# CHEAPO4.net
KiCad netlist of a schematic drawn in EAGLE
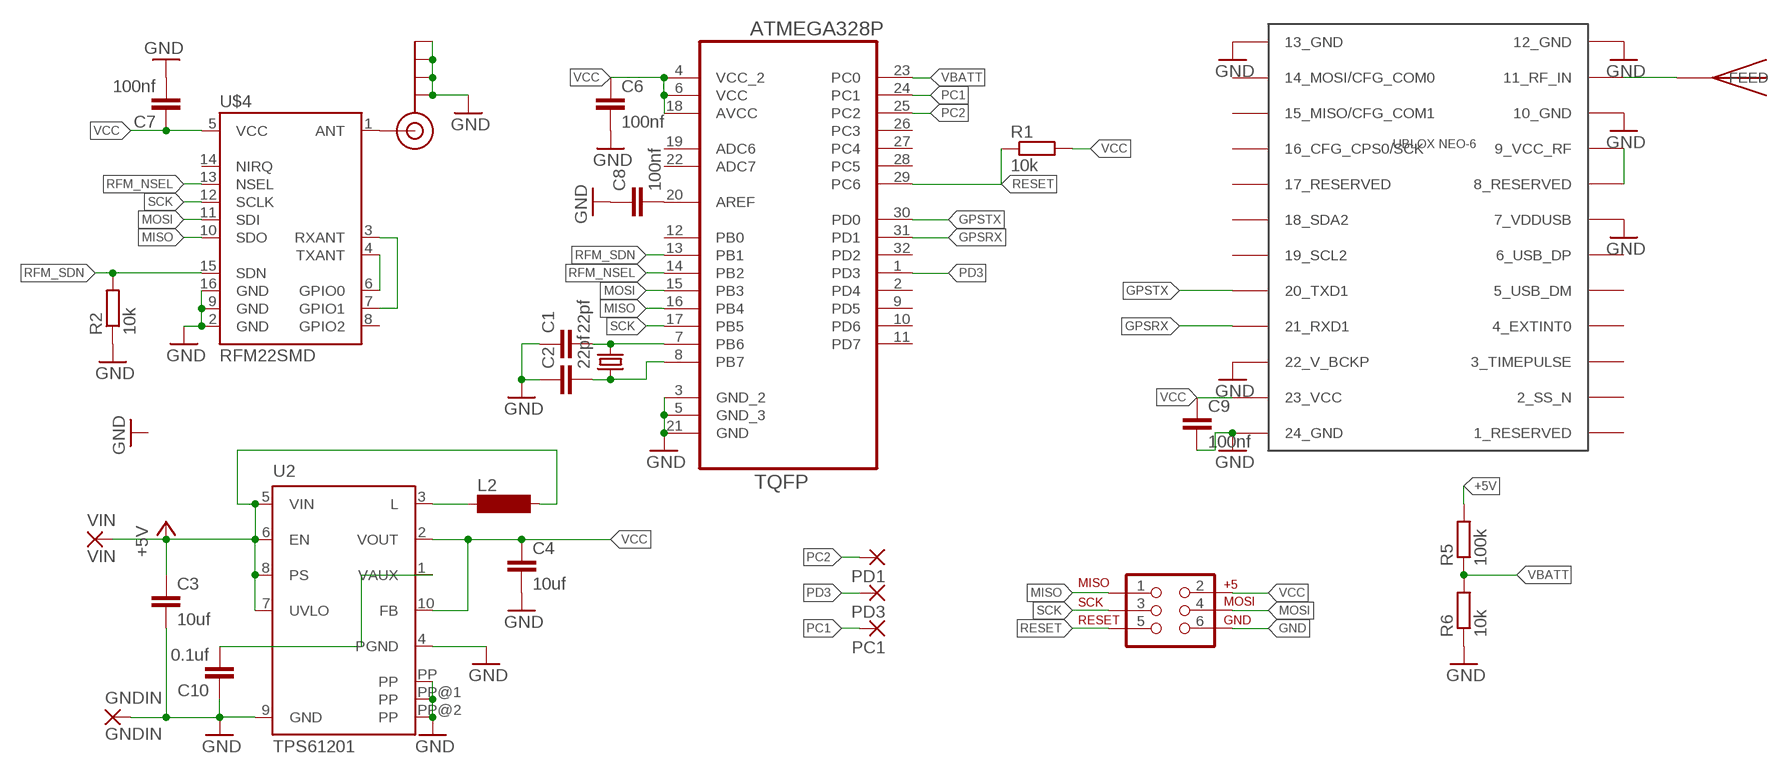
[diagram p0: schematic, sheet 1]

(export (version "E")
  (design (tool "Eeschema 10.0.6"))
  (components
    (comp (ref "C1")
      (value "22pf")
      (footprint "eagle-import:C0603")
      (libsource (lib "eagle-import") (part "C-EUC0603"))
    )
    (comp (ref "C2")
      (value "22pf")
      (footprint "eagle-import:C0603")
      (libsource (lib "eagle-import") (part "C-EUC0603"))
    )
    (comp (ref "C3")
      (value "10uf")
      (footprint "eagle-import:C1206")
      (libsource (lib "eagle-import") (part "C-EUC1206"))
    )
    (comp (ref "C4")
      (value "10uf")
      (footprint "eagle-import:C1206")
      (libsource (lib "eagle-import") (part "C-EUC1206"))
    )
    (comp (ref "C6")
      (value "100nf")
      (footprint "eagle-import:C0603")
      (libsource (lib "eagle-import") (part "C-EUC0603"))
    )
    (comp (ref "C7")
      (value "100nf")
      (footprint "eagle-import:C0603")
      (libsource (lib "eagle-import") (part "C-EUC0603"))
    )
    (comp (ref "C8")
      (value "100nf")
      (footprint "eagle-import:C0603")
      (libsource (lib "eagle-import") (part "C-EUC0603"))
    )
    (comp (ref "C9")
      (value "100nf")
      (footprint "eagle-import:C0603")
      (libsource (lib "eagle-import") (part "C-EUC0603"))
    )
    (comp (ref "C10")
      (value "0.1uf")
      (footprint "eagle-import:C0603")
      (libsource (lib "eagle-import") (part "C-EUC0603"))
    )
    (comp (ref "GNDIN")
      (value "GNDIN")
      (footprint "eagle-import:SMD1,27-2,54")
      (libsource (lib "eagle-import") (part "SMD2"))
    )
    (comp (ref "J$1")
      (value "SMA_EDGE")
      (footprint "eagle-import:SMA-EDGE")
      (libsource (lib "eagle-import") (part "SMA_EDGE"))
    )
    (comp (ref "J1")
      (value "AVR_SPI_PRG_6PTH")
      (footprint "eagle-import:2X3")
      (libsource (lib "eagle-import") (part "AVR_SPI_PRG_6PTH"))
    )
    (comp (ref "L2")
      (value "MS50")
      (footprint "eagle-import:MS50")
      (libsource (lib "eagle-import") (part "MS50"))
    )
    (comp (ref "PC1")
      (value "SMD2")
      (footprint "eagle-import:SMD1,27-2,54")
      (libsource (lib "eagle-import") (part "SMD2"))
    )
    (comp (ref "PD1")
      (value "SMD2")
      (footprint "eagle-import:SMD1,27-2,54")
      (libsource (lib "eagle-import") (part "SMD2"))
    )
    (comp (ref "PD3")
      (value "SMD2")
      (footprint "eagle-import:SMD1,27-2,54")
      (libsource (lib "eagle-import") (part "SMD2"))
    )
    (comp (ref "R1")
      (value "10k")
      (footprint "eagle-import:R0603")
      (libsource (lib "eagle-import") (part "R-EU_R0603"))
    )
    (comp (ref "R2")
      (value "10k")
      (footprint "eagle-import:R0603")
      (libsource (lib "eagle-import") (part "R-EU_R0603"))
    )
    (comp (ref "R5")
      (value "100k")
      (footprint "eagle-import:R0603")
      (libsource (lib "eagle-import") (part "R-EU_R0603"))
    )
    (comp (ref "R6")
      (value "10k")
      (footprint "eagle-import:R0603")
      (libsource (lib "eagle-import") (part "R-EU_R0603"))
    )
    (comp (ref "U$1")
      (value "UBLOX_NEO-6")
      (footprint "eagle-import:UBLOX_NEO-6P")
      (libsource (lib "eagle-import") (part "UBLOX_NEO-6"))
    )
    (comp (ref "U$2")
      (value "ABRACON_ABM3_CRYSTALABM03_HC49")
      (footprint "eagle-import:ABM03_HC49")
      (libsource (lib "eagle-import") (part "ABRACON_ABM3_CRYSTALABM03_HC49"))
    )
    (comp (ref "U$3")
      (value "JTI_ANTENNA-1575AT43A40")
      (footprint "eagle-import:JTI_ANTENNA-1575AT43A40")
      (libsource (lib "eagle-import") (part "JTI_ANTENNA-1575AT43A40"))
    )
    (comp (ref "U$4")
      (value "RFM22SMD")
      (footprint "eagle-import:RFM22-XXX-S2")
      (libsource (lib "eagle-import") (part "RFM22SMD"))
    )
    (comp (ref "U1")
      (value "ATMEGA328P-AU")
      (footprint "eagle-import:QFP80P900X900X120-32N")
      (libsource (lib "eagle-import") (part "ATMEGA328P-AU"))
    )
    (comp (ref "U2")
      (value "TPS61201")
      (footprint "eagle-import:S-PDSO-N10")
      (fields
        (field (name "MPN") "TPS61201DRCT")
        (field (name "MPN_1") "TPS61200DRCT")
        (field (name "OC_FARNELL") "1471238")
        (field (name "OC_NEWARK") "37M0066")
      )
      (libsource (lib "eagle-import") (part "TPS61201"))
    )
    (comp (ref "VIN")
      (value "VIN")
      (footprint "eagle-import:SMD1,27-2,54")
      (libsource (lib "eagle-import") (part "SMD2"))
    )
  )
  (nets
    (net (code "1") (name "+5V") (class "Default")
      (node (ref "C3") (pin "1") (pinfunction "1_1") (pintype "passive"))
      (node (ref "L2") (pin "2") (pinfunction "2_2") (pintype "passive"))
      (node (ref "R5") (pin "2") (pinfunction "2_2") (pintype "passive"))
      (node (ref "U2") (pin "5") (pinfunction "VIN_5") (pintype "input"))
      (node (ref "U2") (pin "6") (pinfunction "EN_6") (pintype "input"))
      (node (ref "U2") (pin "7") (pinfunction "UVLO_7") (pintype "input"))
      (node (ref "U2") (pin "8") (pinfunction "PS_8") (pintype "input"))
      (node (ref "VIN") (pin "1") (pinfunction "P_1") (pintype "passive"))
    )
    (net (code "2") (name "GND") (class "Default")
      (node (ref "C1") (pin "1") (pinfunction "1_1") (pintype "passive"))
      (node (ref "C10") (pin "1") (pinfunction "1_1") (pintype "passive"))
      (node (ref "C2") (pin "1") (pinfunction "1_1") (pintype "passive"))
      (node (ref "C3") (pin "2") (pinfunction "2_2") (pintype "passive"))
      (node (ref "C4") (pin "2") (pinfunction "2_2") (pintype "passive"))
      (node (ref "C6") (pin "2") (pinfunction "2_2") (pintype "passive"))
      (node (ref "C7") (pin "2") (pinfunction "2_2") (pintype "passive"))
      (node (ref "C8") (pin "1") (pinfunction "1_1") (pintype "passive"))
      (node (ref "C9") (pin "2") (pinfunction "2_2") (pintype "passive"))
      (node (ref "GNDIN") (pin "1") (pinfunction "P_1") (pintype "passive"))
      (node (ref "J$1") (pin "GND@0") (pinfunction "GND_GND@0") (pintype "bidirectional"))
      (node (ref "J$1") (pin "GND@1") (pinfunction "GND_GND@1") (pintype "bidirectional"))
      (node (ref "J$1") (pin "GND@2") (pinfunction "GND_GND@2") (pintype "bidirectional"))
      (node (ref "J$1") (pin "GND@3") (pinfunction "GND_GND@3") (pintype "bidirectional"))
      (node (ref "J1") (pin "6") (pinfunction "6_6") (pintype "passive"))
      (node (ref "R2") (pin "1") (pinfunction "1_1") (pintype "passive"))
      (node (ref "R6") (pin "1") (pinfunction "1_1") (pintype "passive"))
      (node (ref "U$1") (pin "10_GND") (pinfunction "10_GND_10_GND") (pintype "bidirectional"))
      (node (ref "U$1") (pin "12_GND") (pinfunction "12_GND_12_GND") (pintype "bidirectional"))
      (node (ref "U$1") (pin "13_GND") (pinfunction "13_GND_13_GND") (pintype "bidirectional"))
      (node (ref "U$1") (pin "22_V_BCKP") (pinfunction "22_V_BCKP_22_V_BCKP") (pintype "bidirectional"))
      (node (ref "U$1") (pin "24_GND") (pinfunction "24_GND_24_GND") (pintype "bidirectional"))
      (node (ref "U$1") (pin "7_VDDUSB") (pinfunction "7_VDDUSB_7_VDDUSB") (pintype "bidirectional"))
      (node (ref "U$4") (pin "16") (pinfunction "GND_16") (pintype "power_in"))
      (node (ref "U$4") (pin "2") (pinfunction "GND_2") (pintype "power_in"))
      (node (ref "U$4") (pin "9") (pinfunction "GND_9") (pintype "power_in"))
      (node (ref "U1") (pin "21") (pinfunction "GND_21") (pintype "passive"))
      (node (ref "U1") (pin "3") (pinfunction "GND_2_3") (pintype "passive"))
      (node (ref "U1") (pin "5") (pinfunction "GND_3_5") (pintype "passive"))
      (node (ref "U2") (pin "4") (pinfunction "PGND_4") (pintype "power_in"))
      (node (ref "U2") (pin "9") (pinfunction "GND_9") (pintype "power_in"))
      (node (ref "U2") (pin "PP") (pinfunction "PP_PP") (pintype "power_in"))
      (node (ref "U2") (pin "PP@1") (pinfunction "PP_PP@1") (pintype "power_in"))
      (node (ref "U2") (pin "PP@2") (pinfunction "PP_PP@2") (pintype "power_in"))
    )
    (net (code "3") (name "GPSRX") (class "Default")
      (node (ref "U$1") (pin "21_RXD1") (pinfunction "21_RXD1_21_RXD1") (pintype "bidirectional"))
      (node (ref "U1") (pin "31") (pinfunction "PD1_31") (pintype "bidirectional"))
    )
    (net (code "4") (name "GPSTX") (class "Default")
      (node (ref "U$1") (pin "20_TXD1") (pinfunction "20_TXD1_20_TXD1") (pintype "bidirectional"))
      (node (ref "U1") (pin "30") (pinfunction "PD0_30") (pintype "bidirectional"))
    )
    (net (code "5") (name "MISO") (class "Default")
      (node (ref "J1") (pin "1") (pinfunction "1_1") (pintype "passive"))
      (node (ref "U$4") (pin "10") (pinfunction "SDO_10") (pintype "output"))
      (node (ref "U1") (pin "16") (pinfunction "PB4_16") (pintype "bidirectional"))
    )
    (net (code "6") (name "MOSI") (class "Default")
      (node (ref "J1") (pin "4") (pinfunction "4_4") (pintype "passive"))
      (node (ref "U$4") (pin "11") (pinfunction "SDI_11") (pintype "input"))
      (node (ref "U1") (pin "15") (pinfunction "PB3_15") (pintype "bidirectional"))
    )
    (net (code "7") (name "Net-(J$1-SIGNAL)") (class "Default")
      (node (ref "J$1") (pin "SIG") (pinfunction "SIGNAL_SIG") (pintype "bidirectional"))
      (node (ref "U$4") (pin "1") (pinfunction "ANT_1") (pintype "bidirectional"))
    )
    (net (code "8") (name "Net-(U$1-Pad8_RESERVED)") (class "Default")
      (node (ref "U$1") (pin "8_RESERVED") (pinfunction "8_RESERVED_8_RESERVED") (pintype "bidirectional"))
      (node (ref "U$1") (pin "9_VCC_RF") (pinfunction "9_VCC_RF_9_VCC_RF") (pintype "bidirectional"))
    )
    (net (code "9") (name "Net-(U$1-Pad11_RF_IN)") (class "Default")
      (node (ref "U$1") (pin "11_RF_IN") (pinfunction "11_RF_IN_11_RF_IN") (pintype "bidirectional"))
      (node (ref "U$3") (pin "FEED") (pinfunction "FEED_FEED") (pintype "bidirectional"))
    )
    (net (code "10") (name "Net-(U$4-GPIO0)") (class "Default")
      (node (ref "U$4") (pin "4") (pinfunction "TXANT_4") (pintype "input"))
      (node (ref "U$4") (pin "6") (pinfunction "GPIO0_6") (pintype "bidirectional"))
    )
    (net (code "11") (name "Net-(U$4-GPIO1)") (class "Default")
      (node (ref "U$4") (pin "3") (pinfunction "RXANT_3") (pintype "input"))
      (node (ref "U$4") (pin "7") (pinfunction "GPIO1_7") (pintype "bidirectional"))
    )
    (net (code "12") (name "Net-(U1-AREF)") (class "Default")
      (node (ref "C8") (pin "2") (pinfunction "2_2") (pintype "passive"))
      (node (ref "U1") (pin "20") (pinfunction "AREF_20") (pintype "input"))
    )
    (net (code "13") (name "Net-(U1-PB6)") (class "Default")
      (node (ref "C1") (pin "2") (pinfunction "2_2") (pintype "passive"))
      (node (ref "U$2") (pin "2") (pinfunction "2_2") (pintype "passive"))
      (node (ref "U1") (pin "7") (pinfunction "PB6_7") (pintype "bidirectional"))
    )
    (net (code "14") (name "Net-(U1-PB7)") (class "Default")
      (node (ref "C2") (pin "2") (pinfunction "2_2") (pintype "passive"))
      (node (ref "U$2") (pin "1") (pinfunction "1_1") (pintype "passive"))
      (node (ref "U1") (pin "8") (pinfunction "PB7_8") (pintype "bidirectional"))
    )
    (net (code "15") (name "Net-(U2-L)") (class "Default")
      (node (ref "L2") (pin "1") (pinfunction "1_1") (pintype "passive"))
      (node (ref "U2") (pin "3") (pinfunction "L_3") (pintype "input"))
    )
    (net (code "16") (name "Net-(U2-VAUX)") (class "Default")
      (node (ref "C10") (pin "2") (pinfunction "2_2") (pintype "passive"))
      (node (ref "U2") (pin "1") (pinfunction "VAUX_1") (pintype "bidirectional"))
    )
    (net (code "17") (name "PC1") (class "Default")
      (node (ref "PC1") (pin "1") (pinfunction "P_1") (pintype "passive"))
      (node (ref "U1") (pin "24") (pinfunction "PC1_24") (pintype "bidirectional"))
    )
    (net (code "18") (name "PC2") (class "Default")
      (node (ref "PD1") (pin "1") (pinfunction "P_1") (pintype "passive"))
      (node (ref "U1") (pin "25") (pinfunction "PC2_25") (pintype "bidirectional"))
    )
    (net (code "19") (name "PD3") (class "Default")
      (node (ref "PD3") (pin "1") (pinfunction "P_1") (pintype "passive"))
      (node (ref "U1") (pin "1") (pinfunction "PD3_1") (pintype "bidirectional"))
    )
    (net (code "20") (name "RESET") (class "Default")
      (node (ref "J1") (pin "5") (pinfunction "5_5") (pintype "passive"))
      (node (ref "R1") (pin "1") (pinfunction "1_1") (pintype "passive"))
      (node (ref "U1") (pin "29") (pinfunction "PC6_29") (pintype "bidirectional"))
    )
    (net (code "21") (name "RFM_NSEL") (class "Default")
      (node (ref "U$4") (pin "13") (pinfunction "NSEL_13") (pintype "input"))
      (node (ref "U1") (pin "14") (pinfunction "PB2_14") (pintype "bidirectional"))
    )
    (net (code "22") (name "RFM_SDN") (class "Default")
      (node (ref "R2") (pin "2") (pinfunction "2_2") (pintype "passive"))
      (node (ref "U$4") (pin "15") (pinfunction "SDN_15") (pintype "input"))
      (node (ref "U1") (pin "13") (pinfunction "PB1_13") (pintype "bidirectional"))
    )
    (net (code "23") (name "SCK") (class "Default")
      (node (ref "J1") (pin "3") (pinfunction "3_3") (pintype "passive"))
      (node (ref "U$4") (pin "12") (pinfunction "SCLK_12") (pintype "input"))
      (node (ref "U1") (pin "17") (pinfunction "PB5_17") (pintype "bidirectional"))
    )
    (net (code "24") (name "VBATT") (class "Default")
      (node (ref "R5") (pin "1") (pinfunction "1_1") (pintype "passive"))
      (node (ref "R6") (pin "2") (pinfunction "2_2") (pintype "passive"))
      (node (ref "U1") (pin "23") (pinfunction "PC0_23") (pintype "bidirectional"))
    )
    (net (code "25") (name "VCC") (class "Default")
      (node (ref "C4") (pin "1") (pinfunction "1_1") (pintype "passive"))
      (node (ref "C6") (pin "1") (pinfunction "1_1") (pintype "passive"))
      (node (ref "C7") (pin "1") (pinfunction "1_1") (pintype "passive"))
      (node (ref "C9") (pin "1") (pinfunction "1_1") (pintype "passive"))
      (node (ref "J1") (pin "2") (pinfunction "2_2") (pintype "passive"))
      (node (ref "R1") (pin "2") (pinfunction "2_2") (pintype "passive"))
      (node (ref "U$1") (pin "23_VCC") (pinfunction "23_VCC_23_VCC") (pintype "bidirectional"))
      (node (ref "U$4") (pin "5") (pinfunction "VCC_5") (pintype "bidirectional"))
      (node (ref "U1") (pin "18") (pinfunction "AVCC_18") (pintype "power_in"))
      (node (ref "U1") (pin "4") (pinfunction "VCC_2_4") (pintype "power_in"))
      (node (ref "U1") (pin "6") (pinfunction "VCC_6") (pintype "power_in"))
      (node (ref "U2") (pin "10") (pinfunction "FB_10") (pintype "input"))
      (node (ref "U2") (pin "2") (pinfunction "VOUT_2") (pintype "passive"))
    )
    (net (code "26") (name "unconnected-(U$1-Pad1_RESERVED)") (class "Default")
      (node (ref "U$1") (pin "1_RESERVED") (pinfunction "1_RESERVED_1_RESERVED") (pintype "bidirectional"))
    )
    (net (code "27") (name "unconnected-(U$1-Pad2_SS_N)") (class "Default")
      (node (ref "U$1") (pin "2_SS_N") (pinfunction "2_SS_N_2_SS_N") (pintype "bidirectional"))
    )
    (net (code "28") (name "unconnected-(U$1-Pad3_TIMEPULSE)") (class "Default")
      (node (ref "U$1") (pin "3_TIMEPULSE") (pinfunction "3_TIMEPULSE_3_TIMEPULSE") (pintype "bidirectional"))
    )
    (net (code "29") (name "unconnected-(U$1-Pad4_EXTINT0)") (class "Default")
      (node (ref "U$1") (pin "4_EXTINT0") (pinfunction "4_EXTINT0_4_EXTINT0") (pintype "bidirectional"))
    )
    (net (code "30") (name "unconnected-(U$1-Pad5_USB_DM)") (class "Default")
      (node (ref "U$1") (pin "5_USB_DM") (pinfunction "5_USB_DM_5_USB_DM") (pintype "bidirectional"))
    )
    (net (code "31") (name "unconnected-(U$1-Pad6_USB_DP)") (class "Default")
      (node (ref "U$1") (pin "6_USB_DP") (pinfunction "6_USB_DP_6_USB_DP") (pintype "bidirectional"))
    )
    (net (code "32") (name "unconnected-(U$1-Pad14_MOSI{slash}CFG_COM0)") (class "Default")
      (node (ref "U$1") (pin "14_MOSI/CFG_COM0") (pinfunction "14_MOSI/CFG_COM0_14_MOSI/CFG_COM0") (pintype "bidirectional"))
    )
    (net (code "33") (name "unconnected-(U$1-Pad15_MISO{slash}CFG_COM1)") (class "Default")
      (node (ref "U$1") (pin "15_MISO/CFG_COM1") (pinfunction "15_MISO/CFG_COM1_15_MISO/CFG_COM1") (pintype "bidirectional"))
    )
    (net (code "34") (name "unconnected-(U$1-Pad16_CFG_CPS0{slash}SCK)") (class "Default")
      (node (ref "U$1") (pin "16_CFG_CPS0/SCK") (pinfunction "16_CFG_CPS0/SCK_16_CFG_CPS0/SCK") (pintype "bidirectional"))
    )
    (net (code "35") (name "unconnected-(U$1-Pad17_RESERVED)") (class "Default")
      (node (ref "U$1") (pin "17_RESERVED") (pinfunction "17_RESERVED_17_RESERVED") (pintype "bidirectional"))
    )
    (net (code "36") (name "unconnected-(U$1-Pad18_SDA2)") (class "Default")
      (node (ref "U$1") (pin "18_SDA2") (pinfunction "18_SDA2_18_SDA2") (pintype "bidirectional"))
    )
    (net (code "37") (name "unconnected-(U$1-Pad19_SCL2)") (class "Default")
      (node (ref "U$1") (pin "19_SCL2") (pinfunction "19_SCL2_19_SCL2") (pintype "bidirectional"))
    )
    (net (code "38") (name "unconnected-(U$4-GPIO2-Pad8)") (class "Default")
      (node (ref "U$4") (pin "8") (pinfunction "GPIO2_8") (pintype "bidirectional"))
    )
    (net (code "39") (name "unconnected-(U$4-NIRQ-Pad14)") (class "Default")
      (node (ref "U$4") (pin "14") (pinfunction "NIRQ_14") (pintype "output"))
    )
    (net (code "40") (name "unconnected-(U1-ADC6-Pad19)") (class "Default")
      (node (ref "U1") (pin "19") (pinfunction "ADC6_19") (pintype "input"))
    )
    (net (code "41") (name "unconnected-(U1-ADC7-Pad22)") (class "Default")
      (node (ref "U1") (pin "22") (pinfunction "ADC7_22") (pintype "input"))
    )
    (net (code "42") (name "unconnected-(U1-PB0-Pad12)") (class "Default")
      (node (ref "U1") (pin "12") (pinfunction "PB0_12") (pintype "bidirectional"))
    )
    (net (code "43") (name "unconnected-(U1-PC3-Pad26)") (class "Default")
      (node (ref "U1") (pin "26") (pinfunction "PC3_26") (pintype "bidirectional"))
    )
    (net (code "44") (name "unconnected-(U1-PC4-Pad27)") (class "Default")
      (node (ref "U1") (pin "27") (pinfunction "PC4_27") (pintype "bidirectional"))
    )
    (net (code "45") (name "unconnected-(U1-PC5-Pad28)") (class "Default")
      (node (ref "U1") (pin "28") (pinfunction "PC5_28") (pintype "bidirectional"))
    )
    (net (code "46") (name "unconnected-(U1-PD2-Pad32)") (class "Default")
      (node (ref "U1") (pin "32") (pinfunction "PD2_32") (pintype "bidirectional"))
    )
    (net (code "47") (name "unconnected-(U1-PD4-Pad2)") (class "Default")
      (node (ref "U1") (pin "2") (pinfunction "PD4_2") (pintype "bidirectional"))
    )
    (net (code "48") (name "unconnected-(U1-PD5-Pad9)") (class "Default")
      (node (ref "U1") (pin "9") (pinfunction "PD5_9") (pintype "bidirectional"))
    )
    (net (code "49") (name "unconnected-(U1-PD6-Pad10)") (class "Default")
      (node (ref "U1") (pin "10") (pinfunction "PD6_10") (pintype "bidirectional"))
    )
    (net (code "50") (name "unconnected-(U1-PD7-Pad11)") (class "Default")
      (node (ref "U1") (pin "11") (pinfunction "PD7_11") (pintype "bidirectional"))
    )
  )
)
